# match5.net
KiCad netlist of a schematic drawn in EAGLE
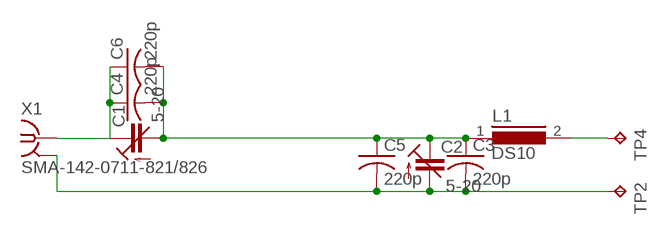
[diagram p0: schematic, sheet 1]

(export (version "E")
  (design (tool "Eeschema 10.0.6"))
  (components
    (comp (ref "C1")
      (value "5-20")
      (footprint "eagle-import:SGC3S")
      (libsource (lib "eagle-import") (part "C-TRIMM"))
    )
    (comp (ref "C2")
      (value "5-20")
      (footprint "eagle-import:SGC3S")
      (libsource (lib "eagle-import") (part "C-TRIMM"))
    )
    (comp (ref "C3")
      (value "220p")
      (footprint "eagle-import:C0805")
      (libsource (lib "eagle-import") (part "C-USC0805"))
    )
    (comp (ref "C4")
      (value "220p")
      (footprint "eagle-import:C0805")
      (libsource (lib "eagle-import") (part "C-USC0805"))
    )
    (comp (ref "C5")
      (value "220p")
      (footprint "eagle-import:C0805")
      (libsource (lib "eagle-import") (part "C-USC0805"))
    )
    (comp (ref "C6")
      (value "220p")
      (footprint "eagle-import:C0805")
      (libsource (lib "eagle-import") (part "C-USC0805"))
    )
    (comp (ref "L1")
      (value "DS10")
      (footprint "eagle-import:DS10")
      (libsource (lib "eagle-import") (part "DS10"))
    )
    (comp (ref "TP2")
      (value "TPPAD1-13Y")
      (footprint "eagle-import:P1-13Y")
      (libsource (lib "eagle-import") (part "TPPAD1-13Y"))
    )
    (comp (ref "TP4")
      (value "TPPAD1-13Y")
      (footprint "eagle-import:P1-13Y")
      (libsource (lib "eagle-import") (part "TPPAD1-13Y"))
    )
    (comp (ref "X1")
      (value "SMA-142-0711-821/826")
      (footprint "eagle-import:J502-ND-142-0711-821_826")
      (fields (field (name "MF") "JOHNSON COMPONENTS") (field (name "MPN") "142-0711-821"))
      (libsource (lib "eagle-import") (part "SMA-142-0711-821/826"))
    )
  )
  (nets
    (net (code "1") (name "Net-(C1-A)") (class "Default")
      (node (ref "C1") (pin "P$1") (pinfunction "A_P$1") (pintype "passive"))
      (node (ref "C2") (pin "P$2") (pinfunction "E_P$2") (pintype "passive"))
      (node (ref "C3") (pin "1") (pinfunction "1_1") (pintype "passive"))
      (node (ref "C4") (pin "2") (pinfunction "2_2") (pintype "passive"))
      (node (ref "C5") (pin "1") (pinfunction "1_1") (pintype "passive"))
      (node (ref "C6") (pin "2") (pinfunction "2_2") (pintype "passive"))
      (node (ref "L1") (pin "1") (pinfunction "1_1") (pintype "passive"))
    )
    (net (code "2") (name "Net-(C1-E)") (class "Default")
      (node (ref "C1") (pin "P$2") (pinfunction "E_P$2") (pintype "passive"))
      (node (ref "C4") (pin "1") (pinfunction "1_1") (pintype "passive"))
      (node (ref "C6") (pin "1") (pinfunction "1_1") (pintype "passive"))
      (node (ref "X1") (pin "1") (pinfunction "1_1") (pintype "passive"))
    )
    (net (code "3") (name "Net-(C2-A)") (class "Default")
      (node (ref "C2") (pin "P$1") (pinfunction "A_P$1") (pintype "passive"))
      (node (ref "C3") (pin "2") (pinfunction "2_2") (pintype "passive"))
      (node (ref "C5") (pin "2") (pinfunction "2_2") (pintype "passive"))
      (node (ref "TP2") (pin "TP") (pinfunction "TP_TP") (pintype "input"))
      (node (ref "X1") (pin "G@1") (pinfunction "2_G@1") (pintype "passive"))
      (node (ref "X1") (pin "G@2") (pinfunction "2_G@2") (pintype "passive"))
      (node (ref "X1") (pin "G@3") (pinfunction "2_G@3") (pintype "passive"))
      (node (ref "X1") (pin "G@4") (pinfunction "2_G@4") (pintype "passive"))
    )
    (net (code "4") (name "Net-(L1-Pad2)") (class "Default")
      (node (ref "L1") (pin "2") (pinfunction "2_2") (pintype "passive"))
      (node (ref "TP4") (pin "TP") (pinfunction "TP_TP") (pintype "input"))
    )
  )
)
